# schematic.net
KiCad netlist of a schematic drawn in EAGLE
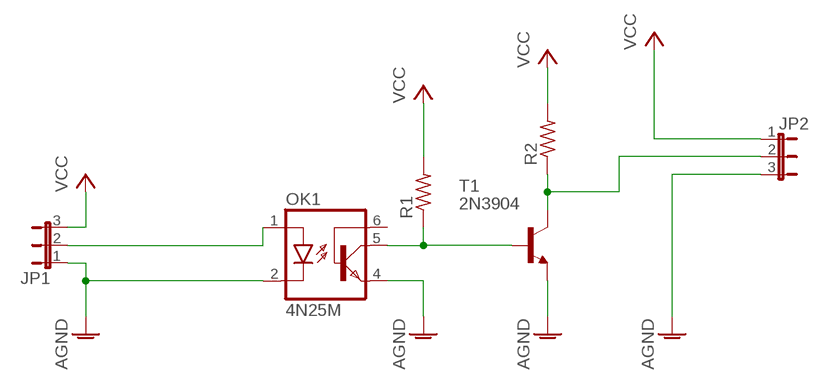
[diagram p0: schematic, sheet 1]

(export (version "E")
  (design (tool "Eeschema 10.0.6"))
  (components
    (comp (ref "JP1")
      (value "JP2E")
      (footprint "eagle-import:JP2")
      (libsource (lib "eagle-import") (part "JP2E"))
    )
    (comp (ref "JP2")
      (value "JP2E")
      (footprint "eagle-import:JP2")
      (libsource (lib "eagle-import") (part "JP2E"))
    )
    (comp (ref "OK1")
      (value "4N25M")
      (footprint "eagle-import:DIL06")
      (fields (field (name "MPN") "4N25-M"))
      (libsource (lib "eagle-import") (part "4N?M25"))
    )
    (comp (ref "R1")
      (value "R-US_0207/10")
      (footprint "eagle-import:0207_10")
      (libsource (lib "eagle-import") (part "R-US_0207/10"))
    )
    (comp (ref "R2")
      (value "R-US_0207/10")
      (footprint "eagle-import:0207_10")
      (libsource (lib "eagle-import") (part "R-US_0207/10"))
    )
    (comp (ref "T1")
      (value "2N3904")
      (footprint "eagle-import:TO92")
      (libsource (lib "eagle-import") (part "2N3904"))
    )
  )
  (nets
    (net (code "1") (name "AGND") (class "Default")
      (node (ref "JP1") (pin "1") (pinfunction "1_1") (pintype "passive"))
      (node (ref "JP2") (pin "3") (pinfunction "3_3") (pintype "passive"))
      (node (ref "OK1") (pin "2") (pinfunction "C_2") (pintype "passive"))
      (node (ref "OK1") (pin "4") (pinfunction "EMI_4") (pintype "passive"))
      (node (ref "T1") (pin "3") (pinfunction "E_3") (pintype "passive"))
    )
    (net (code "2") (name "Net-(OK1-A)") (class "Default")
      (node (ref "JP1") (pin "2") (pinfunction "2_2") (pintype "passive"))
      (node (ref "OK1") (pin "1") (pinfunction "A_1") (pintype "passive"))
    )
    (net (code "3") (name "Net-(OK1-COL)") (class "Default")
      (node (ref "OK1") (pin "5") (pinfunction "COL_5") (pintype "passive"))
      (node (ref "R1") (pin "1") (pinfunction "1_1") (pintype "passive"))
      (node (ref "T1") (pin "2") (pinfunction "B_2") (pintype "passive"))
    )
    (net (code "4") (name "Net-(T1-C)") (class "Default")
      (node (ref "JP2") (pin "2") (pinfunction "2_2") (pintype "passive"))
      (node (ref "R2") (pin "1") (pinfunction "1_1") (pintype "passive"))
      (node (ref "T1") (pin "1") (pinfunction "C_1") (pintype "passive"))
    )
    (net (code "5") (name "VCC") (class "Default")
      (node (ref "JP1") (pin "3") (pinfunction "3_3") (pintype "passive"))
      (node (ref "JP2") (pin "1") (pinfunction "1_1") (pintype "passive"))
      (node (ref "R1") (pin "2") (pinfunction "2_2") (pintype "passive"))
      (node (ref "R2") (pin "2") (pinfunction "2_2") (pintype "passive"))
    )
    (net (code "6") (name "unconnected-(OK1-BAS-Pad6)") (class "Default")
      (node (ref "OK1") (pin "6") (pinfunction "BAS_6") (pintype "passive"))
    )
  )
)
